# MCU.net
KiCad netlist of a schematic drawn in Altium Designer
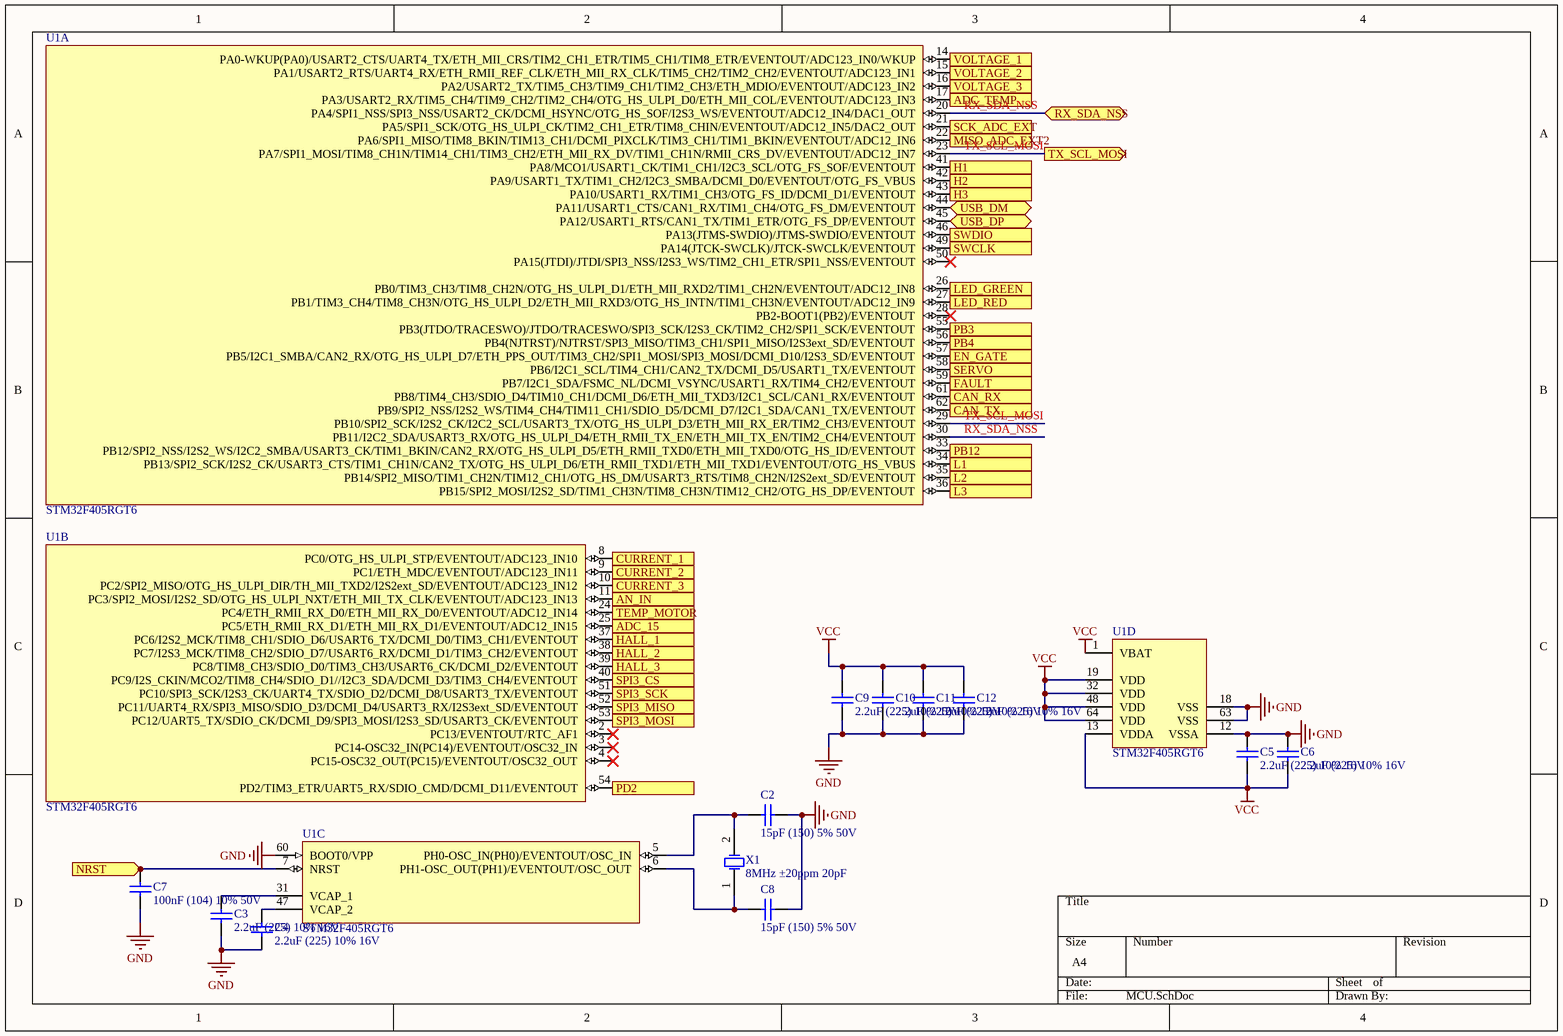
[diagram p0: MCU.SchDoc]

(export (version "E")
  (design (tool "Eeschema 10.0.6"))
  (components
    (comp (ref "C2")
      (value "15pF (150) 5% 50V")
      (footprint "0603_C")
      (description "贴片电容")
      (libsource (lib "Miscellaneous Devices LC") (part "0603 15pF (150) 5% 50V"))
    )
    (comp (ref "C3")
      (value "2.2uF (225) 10% 16V")
      (footprint "0603_C")
      (description "贴片电容")
      (libsource (lib "Miscellaneous Devices LC") (part "0603 2.2uF (225) 10% 16V"))
    )
    (comp (ref "C4")
      (value "2.2uF (225) 10% 16V")
      (footprint "0603_C")
      (description "贴片电容")
      (libsource (lib "Miscellaneous Devices LC") (part "0603 2.2uF (225) 10% 16V"))
    )
    (comp (ref "C5")
      (value "2.2uF (225) 10% 16V")
      (footprint "0603_C")
      (description "贴片电容")
      (libsource (lib "Miscellaneous Devices LC") (part "0603 2.2uF (225) 10% 16V"))
    )
    (comp (ref "C6")
      (value "2.2uF (225) 10% 16V")
      (footprint "0603_C")
      (description "贴片电容")
      (libsource (lib "Miscellaneous Devices LC") (part "0603 2.2uF (225) 10% 16V"))
    )
    (comp (ref "C7")
      (value "100nF (104) 10% 50V")
      (footprint "0603_C")
      (description "贴片电容")
      (libsource (lib "Miscellaneous Devices LC") (part "0603 100nF (104) 10% 50V"))
    )
    (comp (ref "C8")
      (value "15pF (150) 5% 50V")
      (footprint "0603_C")
      (description "贴片电容")
      (libsource (lib "Miscellaneous Devices LC") (part "0603 15pF (150) 5% 50V"))
    )
    (comp (ref "C9")
      (value "2.2uF (225) 10% 16V")
      (footprint "0603_C")
      (description "贴片电容")
      (libsource (lib "Miscellaneous Devices LC") (part "0603 2.2uF (225) 10% 16V"))
    )
    (comp (ref "C10")
      (value "2.2uF (225) 10% 16V")
      (footprint "0603_C")
      (description "贴片电容")
      (libsource (lib "Miscellaneous Devices LC") (part "0603 2.2uF (225) 10% 16V"))
    )
    (comp (ref "C11")
      (value "2.2uF (225) 10% 16V")
      (footprint "0603_C")
      (description "贴片电容")
      (libsource (lib "Miscellaneous Devices LC") (part "0603 2.2uF (225) 10% 16V"))
    )
    (comp (ref "C12")
      (value "2.2uF (225) 10% 16V")
      (footprint "0603_C")
      (description "贴片电容")
      (libsource (lib "Miscellaneous Devices LC") (part "0603 2.2uF (225) 10% 16V"))
    )
    (comp (ref "U1")
      (value "STM32F405RGT6")
      (footprint "LQFP-64_10x10x05P")
      (description "ARM")
      (libsource (lib "Miscellaneous Devices LC") (part "STM32F405RGT6"))
    )
    (comp (ref "X1")
      (value "8MHz ±20ppm 20pF")
      (footprint "SMD-5032_2P")
      (description "贴片晶振")
      (libsource (lib "Miscellaneous Devices LC") (part "SMD-5032_2P 8MHz 20ppm 20pF"))
    )
  )
  (nets
    (net (code "1") (name "/ADC_15") (class "Default")
      (node (ref "U1") (pin "25") (pinfunction "PC5/ETH_RMII_RX_D1/ETH_MII_RX_D1/EVENTOUT/ADC12_IN15_25") (pintype "bidirectional"))
    )
    (net (code "2") (name "/ADC_TEMP") (class "Default")
      (node (ref "U1") (pin "17") (pinfunction "PA3/USART2_RX/TIM5_CH4/TIM9_CH2/TIM2_CH4/OTG_HS_ULPI_D0/ETH_MII_COL/EVENTOUT/ADC123_IN3_17") (pintype "bidirectional"))
    )
    (net (code "3") (name "/AN_IN") (class "Default")
      (node (ref "U1") (pin "11") (pinfunction "PC3/SPI2_MOSI/I2S2_SD/OTG_HS_ULPI_NXT/ETH_MII_TX_CLK/EVENTOUT/ADC123_IN13_11") (pintype "bidirectional"))
    )
    (net (code "4") (name "/CAN_RX") (class "Default")
      (node (ref "U1") (pin "61") (pinfunction "PB8/TIM4_CH3/SDIO_D4/TIM10_CH1/DCMI_D6/ETH_MII_TXD3/I2C1_SCL/CAN1_RX/EVENTOUT_61") (pintype "bidirectional"))
    )
    (net (code "5") (name "/CAN_TX") (class "Default")
      (node (ref "U1") (pin "62") (pinfunction "PB9/SPI2_NSS/I2S2_WS/TIM4_CH4/TIM11_CH1/SDIO_D5/DCMI_D7/I2C1_SDA/CAN1_TX/EVENTOUT_62") (pintype "bidirectional"))
    )
    (net (code "6") (name "/CURRENT_1") (class "Default")
      (node (ref "U1") (pin "8") (pinfunction "PC0/OTG_HS_ULPI_STP/EVENTOUT/ADC123_IN10_8") (pintype "bidirectional"))
    )
    (net (code "7") (name "/CURRENT_2") (class "Default")
      (node (ref "U1") (pin "9") (pinfunction "PC1/ETH_MDC/EVENTOUT/ADC123_IN11_9") (pintype "bidirectional"))
    )
    (net (code "8") (name "/CURRENT_3") (class "Default")
      (node (ref "U1") (pin "10") (pinfunction "PC2/SPI2_MISO/OTG_HS_ULPI_DIR/TH_MII_TXD2/I2S2ext_SD/EVENTOUT/ADC123_IN12_10") (pintype "bidirectional"))
    )
    (net (code "9") (name "/EN_GATE") (class "Default")
      (node (ref "U1") (pin "57") (pinfunction "PB5/I2C1_SMBA/CAN2_RX/OTG_HS_ULPI_D7/ETH_PPS_OUT/TIM3_CH2/SPI1_MOSI/SPI3_MOSI/DCMI_D10/I2S3_SD/EVENTOUT_57") (pintype "bidirectional"))
    )
    (net (code "10") (name "/FAULT") (class "Default")
      (node (ref "U1") (pin "59") (pinfunction "PB7/I2C1_SDA/FSMC_NL/DCMI_VSYNC/USART1_RX/TIM4_CH2/EVENTOUT_59") (pintype "bidirectional"))
    )
    (net (code "11") (name "/H1") (class "Default")
      (node (ref "U1") (pin "41") (pinfunction "PA8/MCO1/USART1_CK/TIM1_CH1/I2C3_SCL/OTG_FS_SOF/EVENTOUT_41") (pintype "bidirectional"))
    )
    (net (code "12") (name "/H2") (class "Default")
      (node (ref "U1") (pin "42") (pinfunction "PA9/USART1_TX/TIM1_CH2/I2C3_SMBA/DCMI_D0/EVENTOUT/OTG_FS_VBUS_42") (pintype "bidirectional"))
    )
    (net (code "13") (name "/H3") (class "Default")
      (node (ref "U1") (pin "43") (pinfunction "PA10/USART1_RX/TIM1_CH3/OTG_FS_ID/DCMI_D1/EVENTOUT_43") (pintype "bidirectional"))
    )
    (net (code "14") (name "/HALL_1") (class "Default")
      (node (ref "U1") (pin "37") (pinfunction "PC6/I2S2_MCK/TIM8_CH1/SDIO_D6/USART6_TX/DCMI_D0/TIM3_CH1/EVENTOUT_37") (pintype "bidirectional"))
    )
    (net (code "15") (name "/HALL_2") (class "Default")
      (node (ref "U1") (pin "38") (pinfunction "PC7/I2S3_MCK/TIM8_CH2/SDIO_D7/USART6_RX/DCMI_D1/TIM3_CH2/EVENTOUT_38") (pintype "bidirectional"))
    )
    (net (code "16") (name "/HALL_3") (class "Default")
      (node (ref "U1") (pin "39") (pinfunction "PC8/TIM8_CH3/SDIO_D0/TIM3_CH3/USART6_CK/DCMI_D2/EVENTOUT_39") (pintype "bidirectional"))
    )
    (net (code "17") (name "/L1") (class "Default")
      (node (ref "U1") (pin "34") (pinfunction "PB13/SPI2_SCK/I2S2_CK/USART3_CTS/TIM1_CH1N/CAN2_TX/OTG_HS_ULPI_D6/ETH_RMII_TXD1/ETH_MII_TXD1/EVENTOUT/OTG_HS_VBUS_34") (pintype "bidirectional"))
    )
    (net (code "18") (name "/L2") (class "Default")
      (node (ref "U1") (pin "35") (pinfunction "PB14/SPI2_MISO/TIM1_CH2N/TIM12_CH1/OTG_HS_DM/USART3_RTS/TIM8_CH2N/I2S2ext_SD/EVENTOUT_35") (pintype "bidirectional"))
    )
    (net (code "19") (name "/L3") (class "Default")
      (node (ref "U1") (pin "36") (pinfunction "PB15/SPI2_MOSI/I2S2_SD/TIM1_CH3N/TIM8_CH3N/TIM12_CH2/OTG_HS_DP/EVENTOUT_36") (pintype "bidirectional"))
    )
    (net (code "20") (name "/LED_GREEN") (class "Default")
      (node (ref "U1") (pin "26") (pinfunction "PB0/TIM3_CH3/TIM8_CH2N/OTG_HS_ULPI_D1/ETH_MII_RXD2/TIM1_CH2N/EVENTOUT/ADC12_IN8_26") (pintype "bidirectional"))
    )
    (net (code "21") (name "/LED_RED") (class "Default")
      (node (ref "U1") (pin "27") (pinfunction "PB1/TIM3_CH4/TIM8_CH3N/OTG_HS_ULPI_D2/ETH_MII_RXD3/OTG_HS_INTN/TIM1_CH3N/EVENTOUT/ADC12_IN9_27") (pintype "bidirectional"))
    )
    (net (code "22") (name "/MISO_ADC_EXT2") (class "Default")
      (node (ref "U1") (pin "22") (pinfunction "PA6/SPI1_MISO/TIM8_BKIN/TIM13_CH1/DCMI_PIXCLK/TIM3_CH1/TIM1_BKIN/EVENTOUT/ADC12_IN6_22") (pintype "bidirectional"))
    )
    (net (code "23") (name "/NRST") (class "Default")
      (node (ref "C7") (pin "2") (pinfunction "2_2") (pintype "passive"))
      (node (ref "U1") (pin "7") (pinfunction "NRST_7") (pintype "bidirectional"))
    )
    (net (code "24") (name "/PB3") (class "Default")
      (node (ref "U1") (pin "55") (pinfunction "PB3(JTDO/TRACESWO)/JTDO/TRACESWO/SPI3_SCK/I2S3_CK/TIM2_CH2/SPI1_SCK/EVENTOUT_55") (pintype "bidirectional"))
    )
    (net (code "25") (name "/PB4") (class "Default")
      (node (ref "U1") (pin "56") (pinfunction "PB4(NJTRST)/NJTRST/SPI3_MISO/TIM3_CH1/SPI1_MISO/I2S3ext_SD/EVENTOUT_56") (pintype "bidirectional"))
    )
    (net (code "26") (name "/PB12") (class "Default")
      (node (ref "U1") (pin "33") (pinfunction "PB12/SPI2_NSS/I2S2_WS/I2C2_SMBA/USART3_CK/TIM1_BKIN/CAN2_RX/OTG_HS_ULPI_D5/ETH_RMII_TXD0/ETH_MII_TXD0/OTG_HS_ID/EVENTOUT_33") (pintype "bidirectional"))
    )
    (net (code "27") (name "/PD2") (class "Default")
      (node (ref "U1") (pin "54") (pinfunction "PD2/TIM3_ETR/UART5_RX/SDIO_CMD/DCMI_D11/EVENTOUT_54") (pintype "bidirectional"))
    )
    (net (code "28") (name "/RX_SDA_NSS") (class "Default")
      (node (ref "U1") (pin "20") (pinfunction "PA4/SPI1_NSS/SPI3_NSS/USART2_CK/DCMI_HSYNC/OTG_HS_SOF/I2S3_WS/EVENTOUT/ADC12_IN4/DAC1_OUT_20") (pintype "bidirectional"))
      (node (ref "U1") (pin "30") (pinfunction "PB11/I2C2_SDA/USART3_RX/OTG_HS_ULPI_D4/ETH_RMII_TX_EN/ETH_MII_TX_EN/TIM2_CH4/EVENTOUT_30") (pintype "bidirectional"))
    )
    (net (code "29") (name "/SCK_ADC_EXT") (class "Default")
      (node (ref "U1") (pin "21") (pinfunction "PA5/SPI1_SCK/OTG_HS_ULPI_CK/TIM2_CH1_ETR/TIM8_CHIN/EVENTOUT/ADC12_IN5/DAC2_OUT_21") (pintype "bidirectional"))
    )
    (net (code "30") (name "/SERVO") (class "Default")
      (node (ref "U1") (pin "58") (pinfunction "PB6/I2C1_SCL/TIM4_CH1/CAN2_TX/DCMI_D5/USART1_TX/EVENTOUT_58") (pintype "bidirectional"))
    )
    (net (code "31") (name "/SPI3_CS") (class "Default")
      (node (ref "U1") (pin "40") (pinfunction "PC9/I2S_CKIN/MCO2/TIM8_CH4/SDIO_D1//I2C3_SDA/DCMI_D3/TIM3_CH4/EVENTOUT_40") (pintype "bidirectional"))
    )
    (net (code "32") (name "/SPI3_MISO") (class "Default")
      (node (ref "U1") (pin "52") (pinfunction "PC11/UART4_RX/SPI3_MISO/SDIO_D3/DCMI_D4/USART3_RX/I2S3ext_SD/EVENTOUT_52") (pintype "bidirectional"))
    )
    (net (code "33") (name "/SPI3_MOSI") (class "Default")
      (node (ref "U1") (pin "53") (pinfunction "PC12/UART5_TX/SDIO_CK/DCMI_D9/SPI3_MOSI/I2S3_SD/USART3_CK/EVENTOUT_53") (pintype "bidirectional"))
    )
    (net (code "34") (name "/SPI3_SCK") (class "Default")
      (node (ref "U1") (pin "51") (pinfunction "PC10/SPI3_SCK/I2S3_CK/UART4_TX/SDIO_D2/DCMI_D8/USART3_TX/EVENTOUT_51") (pintype "bidirectional"))
    )
    (net (code "35") (name "/SWCLK") (class "Default")
      (node (ref "U1") (pin "49") (pinfunction "PA14(JTCK-SWCLK)/JTCK-SWCLK/EVENTOUT_49") (pintype "bidirectional"))
    )
    (net (code "36") (name "/SWDIO") (class "Default")
      (node (ref "U1") (pin "46") (pinfunction "PA13(JTMS-SWDIO)/JTMS-SWDIO/EVENTOUT_46") (pintype "bidirectional"))
    )
    (net (code "37") (name "/TEMP_MOTOR") (class "Default")
      (node (ref "U1") (pin "24") (pinfunction "PC4/ETH_RMII_RX_D0/ETH_MII_RX_D0/EVENTOUT/ADC12_IN14_24") (pintype "bidirectional"))
    )
    (net (code "38") (name "/TX_SCL_MOSI") (class "Default")
      (node (ref "U1") (pin "23") (pinfunction "PA7/SPI1_MOSI/TIM8_CH1N/TIM14_CH1/TIM3_CH2/ETH_MII_RX_DV/TIM1_CH1N/RMII_CRS_DV/EVENTOUT/ADC12_IN7_23") (pintype "bidirectional"))
      (node (ref "U1") (pin "29") (pinfunction "PB10/SPI2_SCK/I2S2_CK/I2C2_SCL/USART3_TX/OTG_HS_ULPI_D3/ETH_MII_RX_ER/TIM2_CH3/EVENTOUT_29") (pintype "bidirectional"))
    )
    (net (code "39") (name "/USB_DM") (class "Default")
      (node (ref "U1") (pin "44") (pinfunction "PA11/USART1_CTS/CAN1_RX/TIM1_CH4/OTG_FS_DM/EVENTOUT_44") (pintype "bidirectional"))
    )
    (net (code "40") (name "/USB_DP") (class "Default")
      (node (ref "U1") (pin "45") (pinfunction "PA12/USART1_RTS/CAN1_TX/TIM1_ETR/OTG_FS_DP/EVENTOUT_45") (pintype "bidirectional"))
    )
    (net (code "41") (name "/VOLTAGE_1") (class "Default")
      (node (ref "U1") (pin "14") (pinfunction "PA0-WKUP(PA0)/USART2_CTS/UART4_TX/ETH_MII_CRS/TIM2_CH1_ETR/TIM5_CH1/TIM8_ETR/EVENTOUT/ADC123_IN0/WKUP_14") (pintype "bidirectional"))
    )
    (net (code "42") (name "/VOLTAGE_2") (class "Default")
      (node (ref "U1") (pin "15") (pinfunction "PA1/USART2_RTS/UART4_RX/ETH_RMII_REF_CLK/ETH_MII_RX_CLK/TIM5_CH2/TIM2_CH2/EVENTOUT/ADC123_IN1_15") (pintype "bidirectional"))
    )
    (net (code "43") (name "/VOLTAGE_3") (class "Default")
      (node (ref "U1") (pin "16") (pinfunction "PA2/USART2_TX/TIM5_CH3/TIM9_CH1/TIM2_CH3/ETH_MDIO/EVENTOUT/ADC123_IN2_16") (pintype "bidirectional"))
    )
    (net (code "44") (name "GND") (class "Default")
      (node (ref "C10") (pin "1") (pinfunction "1_1") (pintype "passive"))
      (node (ref "C11") (pin "1") (pinfunction "1_1") (pintype "passive"))
      (node (ref "C12") (pin "1") (pinfunction "1_1") (pintype "passive"))
      (node (ref "C2") (pin "2") (pinfunction "2_2") (pintype "passive"))
      (node (ref "C3") (pin "1") (pinfunction "1_1") (pintype "passive"))
      (node (ref "C4") (pin "1") (pinfunction "1_1") (pintype "passive"))
      (node (ref "C5") (pin "2") (pinfunction "2_2") (pintype "passive"))
      (node (ref "C6") (pin "2") (pinfunction "2_2") (pintype "passive"))
      (node (ref "C7") (pin "1") (pinfunction "1_1") (pintype "passive"))
      (node (ref "C8") (pin "2") (pinfunction "2_2") (pintype "passive"))
      (node (ref "C9") (pin "1") (pinfunction "1_1") (pintype "passive"))
      (node (ref "U1") (pin "12") (pinfunction "VSSA_12") (pintype "power_in"))
      (node (ref "U1") (pin "18") (pinfunction "VSS_18") (pintype "power_in"))
      (node (ref "U1") (pin "60") (pinfunction "BOOT0/VPP_60") (pintype "input"))
      (node (ref "U1") (pin "63") (pinfunction "VSS_63") (pintype "power_in"))
    )
    (net (code "45") (name "Net-(U1C-PH0-OSC_IN(PH0){slash}EVENTOUT{slash}OSC_IN)") (class "Default")
      (node (ref "C2") (pin "1") (pinfunction "1_1") (pintype "passive"))
      (node (ref "U1") (pin "5") (pinfunction "PH0-OSC_IN(PH0)/EVENTOUT/OSC_IN_5") (pintype "bidirectional"))
      (node (ref "X1") (pin "2") (pinfunction "OSC2_2") (pintype "passive"))
    )
    (net (code "46") (name "Net-(U1C-PH1-OSC_OUT(PH1){slash}EVENTOUT{slash}OSC_OUT)") (class "Default")
      (node (ref "C8") (pin "1") (pinfunction "1_1") (pintype "passive"))
      (node (ref "U1") (pin "6") (pinfunction "PH1-OSC_OUT(PH1)/EVENTOUT/OSC_OUT_6") (pintype "bidirectional"))
      (node (ref "X1") (pin "1") (pinfunction "OSC1_1") (pintype "passive"))
    )
    (net (code "47") (name "Net-(U1C-VCAP_1)") (class "Default")
      (node (ref "C3") (pin "2") (pinfunction "2_2") (pintype "passive"))
      (node (ref "U1") (pin "31") (pinfunction "VCAP_1_31") (pintype "power_in"))
    )
    (net (code "48") (name "Net-(U1C-VCAP_2)") (class "Default")
      (node (ref "C4") (pin "2") (pinfunction "2_2") (pintype "passive"))
      (node (ref "U1") (pin "47") (pinfunction "VCAP_2_47") (pintype "power_in"))
    )
    (net (code "49") (name "VCC") (class "Default")
      (node (ref "C10") (pin "2") (pinfunction "2_2") (pintype "passive"))
      (node (ref "C11") (pin "2") (pinfunction "2_2") (pintype "passive"))
      (node (ref "C12") (pin "2") (pinfunction "2_2") (pintype "passive"))
      (node (ref "C5") (pin "1") (pinfunction "1_1") (pintype "passive"))
      (node (ref "C6") (pin "1") (pinfunction "1_1") (pintype "passive"))
      (node (ref "C9") (pin "2") (pinfunction "2_2") (pintype "passive"))
      (node (ref "U1") (pin "1") (pinfunction "VBAT_1") (pintype "power_in"))
      (node (ref "U1") (pin "13") (pinfunction "VDDA_13") (pintype "power_in"))
      (node (ref "U1") (pin "19") (pinfunction "VDD_19") (pintype "power_in"))
      (node (ref "U1") (pin "32") (pinfunction "VDD_32") (pintype "power_in"))
      (node (ref "U1") (pin "48") (pinfunction "VDD_48") (pintype "power_in"))
      (node (ref "U1") (pin "64") (pinfunction "VDD_64") (pintype "power_in"))
    )
    (net (code "50") (name "unconnected-(U1A-PA15(JTDI){slash}JTDI{slash}SPI3_NSS{slash}I2S3_WS{slash}TIM2_CH1_ETR{slash}SPI1_NSS{slash}EVENTOUT-Pad50)") (class "Default")
      (node (ref "U1") (pin "50") (pinfunction "PA15(JTDI)/JTDI/SPI3_NSS/I2S3_WS/TIM2_CH1_ETR/SPI1_NSS/EVENTOUT_50") (pintype "bidirectional+no_connect"))
    )
    (net (code "51") (name "unconnected-(U1A-PB2-BOOT1(PB2){slash}EVENTOUT-Pad28)") (class "Default")
      (node (ref "U1") (pin "28") (pinfunction "PB2-BOOT1(PB2)/EVENTOUT_28") (pintype "bidirectional+no_connect"))
    )
    (net (code "52") (name "unconnected-(U1B-PC13{slash}EVENTOUT{slash}RTC_AF1-Pad2)") (class "Default")
      (node (ref "U1") (pin "2") (pinfunction "PC13/EVENTOUT/RTC_AF1_2") (pintype "bidirectional+no_connect"))
    )
    (net (code "53") (name "unconnected-(U1B-PC14-OSC32_IN(PC14){slash}EVENTOUT{slash}OSC32_IN-Pad3)") (class "Default")
      (node (ref "U1") (pin "3") (pinfunction "PC14-OSC32_IN(PC14)/EVENTOUT/OSC32_IN_3") (pintype "bidirectional+no_connect"))
    )
    (net (code "54") (name "unconnected-(U1B-PC15-OSC32_OUT(PC15){slash}EVENTOUT{slash}OSC32_OUT-Pad4)") (class "Default")
      (node (ref "U1") (pin "4") (pinfunction "PC15-OSC32_OUT(PC15)/EVENTOUT/OSC32_OUT_4") (pintype "bidirectional+no_connect"))
    )
  )
)
